# ac-dc-converter-hw.net
KiCad netlist of a schematic drawn in Altium Designer
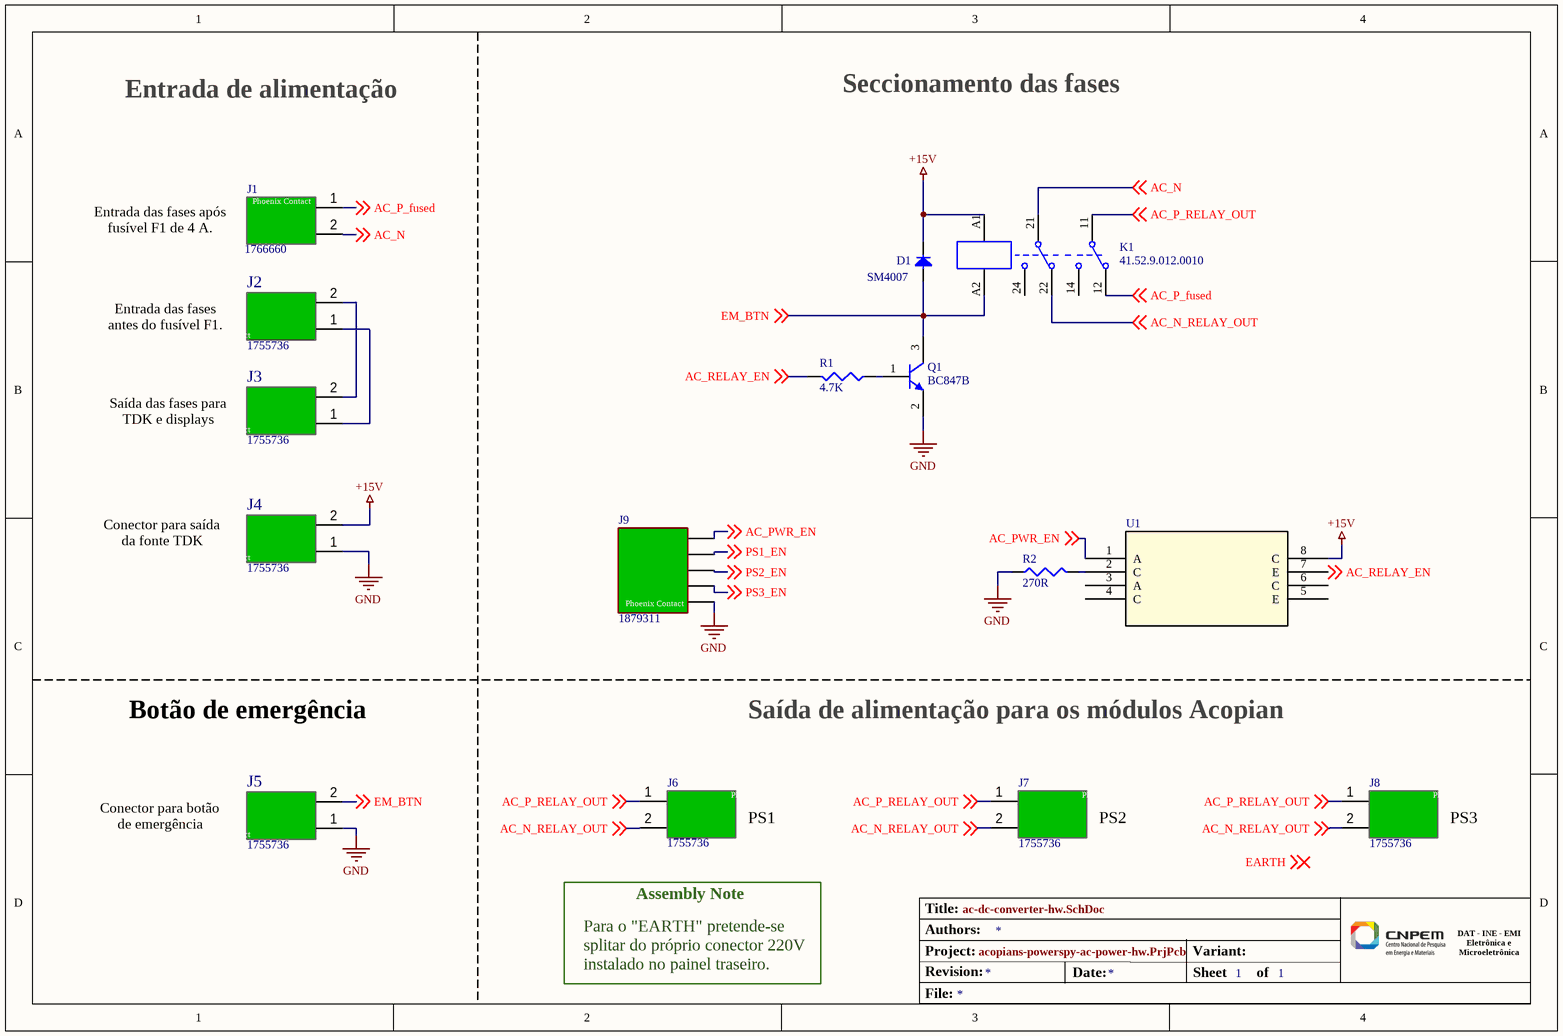
[diagram p0: ac-dc-converter-hw.SchDoc]

(export (version "E")
  (design (tool "Eeschema 10.0.6"))
  (components
    (comp (ref "D1")
      (value "SM4007")
      (footprint "SM4007")
      (libsource (lib "acopians-powerspy-ac-power-hw-library-schematic") (part "SM4007"))
    )
    (comp (ref "J1")
      (value "1766660")
      (footprint "Conector 2 vias espaÃ§ado")
      (description "Pitch 7.5mm")
      (libsource (lib "acopians-powerspy-ac-power-hw-library-schematic") (part "Conector Phoenix 2 vias_espaçado"))
    )
    (comp (ref "J2")
      (value "1755736")
      (footprint "Conector 2 vias")
      (libsource (lib "acopians-powerspy-ac-power-hw-library-schematic") (part "Conector Phoenix 2 vias"))
    )
    (comp (ref "J3")
      (value "1755736")
      (footprint "Conector 2 vias")
      (libsource (lib "acopians-powerspy-ac-power-hw-library-schematic") (part "Conector Phoenix 2 vias"))
    )
    (comp (ref "J4")
      (value "1755736")
      (footprint "Conector 2 vias")
      (libsource (lib "acopians-powerspy-ac-power-hw-library-schematic") (part "Conector Phoenix 2 vias"))
    )
    (comp (ref "J5")
      (value "1755736")
      (footprint "Conector 2 vias")
      (libsource (lib "acopians-powerspy-ac-power-hw-library-schematic") (part "Conector Phoenix 2 vias"))
    )
    (comp (ref "J6")
      (value "1755736")
      (footprint "Conector 2 vias")
      (libsource (lib "") (part "Conector Phoenix 2 vias_1"))
    )
    (comp (ref "J7")
      (value "1755736")
      (footprint "Conector 2 vias")
      (libsource (lib "") (part "Conector Phoenix 2 vias_1"))
    )
    (comp (ref "J8")
      (value "1755736")
      (footprint "Conector 2 vias")
      (libsource (lib "") (part "Conector Phoenix 2 vias_1"))
    )
    (comp (ref "J9")
      (value "1879311")
      (footprint "Conector Phoenix 5 vias 1879311")
      (description "Conector Phoenix 5 vias 1879311")
      (libsource (lib "acopians-powerspy-ac-power-hw-library-schematic") (part "CONECTOR PHOENIX 5 VIAS 1879311"))
    )
    (comp (ref "K1")
      (value "41.52.9.012.0010")
      (footprint "41.52.9.005.0010")
      (description "Low Profile PCB Relay, 2 CO DPDT, 8A, Coil: 12VDC")
      (libsource (lib "acopians-powerspy-ac-power-hw-library-schematic") (part "41.52.9.012.0010"))
    )
    (comp (ref "Q1")
      (value "BC847B")
      (footprint "INF-SOT23_L")
      (description "NPN Silicon AF Transistor, 45 V VCEO, 100 mA IC, SOT23, Reel, Green")
      (fields (field (name "MANUFACTURER") "Infineon"))
      (libsource (lib "Altium Content Vault") (part "INF-BJTNPN-BEC-3"))
    )
    (comp (ref "R1")
      (value "4.7K")
      (footprint "R0603")
      (description "MCT06030C4701FP500")
      (libsource (lib "acopians-powerspy-ac-power-hw-library-schematic") (part "Resistor Generic"))
    )
    (comp (ref "R2")
      (value "270R")
      (footprint "R0603")
      (description "Resistor SMD 270 OHM 1% 1/10W 0603")
      (fields (field (name "TOLERANCE") "1%"))
      (libsource (lib "acopians-monitoring-hw-library-schematic") (part "RESISTOR 270R"))
    )
    (comp (ref "U1")
      (value "~")
      (footprint "SO-8_ILD")
      (description "No Description Available")
      (libsource (lib "acopians-powerspy-ac-power-hw-library-schematic") (part "ILD217T"))
    )
  )
  (nets
    (net (code "1") (name "+15V") (class "Default")
      (node (ref "D1") (pin "1") (pintype "passive"))
      (node (ref "J4") (pin "2") (pinfunction "2_2") (pintype "passive"))
      (node (ref "K1") (pin "A1") (pinfunction "A1_A1") (pintype "passive"))
      (node (ref "U1") (pin "8") (pinfunction "C_8") (pintype "passive"))
    )
    (net (code "2") (name "AC_N") (class "Default")
      (node (ref "J1") (pin "2") (pinfunction "2_2") (pintype "passive"))
      (node (ref "K1") (pin "21") (pinfunction "21_21") (pintype "passive"))
    )
    (net (code "3") (name "AC_N_RELAY_OUT") (class "Default")
      (node (ref "J6") (pin "2") (pinfunction "2_2") (pintype "passive"))
      (node (ref "J7") (pin "2") (pinfunction "2_2") (pintype "passive"))
      (node (ref "J8") (pin "2") (pinfunction "2_2") (pintype "passive"))
      (node (ref "K1") (pin "22") (pinfunction "22_22") (pintype "passive"))
    )
    (net (code "4") (name "AC_PWR_EN") (class "Default")
      (node (ref "J9") (pin "1") (pinfunction "1_1") (pintype "passive"))
      (node (ref "U1") (pin "1") (pinfunction "A_1") (pintype "passive"))
    )
    (net (code "5") (name "AC_P_RELAY_OUT") (class "Default")
      (node (ref "J6") (pin "1") (pinfunction "1_1") (pintype "passive"))
      (node (ref "J7") (pin "1") (pinfunction "1_1") (pintype "passive"))
      (node (ref "J8") (pin "1") (pinfunction "1_1") (pintype "passive"))
      (node (ref "K1") (pin "11") (pinfunction "11_11") (pintype "passive"))
    )
    (net (code "6") (name "AC_P_fused") (class "Default")
      (node (ref "J1") (pin "1") (pinfunction "1_1") (pintype "passive"))
      (node (ref "K1") (pin "12") (pinfunction "12_12") (pintype "passive"))
    )
    (net (code "7") (name "AC_RELAY_EN") (class "Default")
      (node (ref "R1") (pin "2") (pinfunction "2_2") (pintype "passive"))
      (node (ref "U1") (pin "7") (pinfunction "E_7") (pintype "passive"))
    )
    (net (code "9") (name "EM_BTN") (class "Default")
      (node (ref "D1") (pin "2") (pintype "passive"))
      (node (ref "J5") (pin "2") (pinfunction "2_2") (pintype "passive"))
      (node (ref "K1") (pin "A2") (pinfunction "A2_A2") (pintype "passive"))
      (node (ref "Q1") (pin "3") (pinfunction "C_3") (pintype "passive"))
    )
    (net (code "10") (name "GND") (class "Default")
      (node (ref "J4") (pin "1") (pinfunction "1_1") (pintype "passive"))
      (node (ref "J5") (pin "1") (pinfunction "1_1") (pintype "passive"))
      (node (ref "J9") (pin "5") (pinfunction "5_5") (pintype "passive"))
      (node (ref "Q1") (pin "2") (pinfunction "E_2") (pintype "passive"))
      (node (ref "R2") (pin "1") (pinfunction "1_1") (pintype "passive"))
    )
    (net (code "11") (name "Net-(J2-Pad1)") (class "Default")
      (node (ref "J2") (pin "1") (pinfunction "1_1") (pintype "passive"))
      (node (ref "J3") (pin "1") (pinfunction "1_1") (pintype "passive"))
    )
    (net (code "12") (name "Net-(J2-Pad2)") (class "Default")
      (node (ref "J2") (pin "2") (pinfunction "2_2") (pintype "passive"))
      (node (ref "J3") (pin "2") (pinfunction "2_2") (pintype "passive"))
    )
    (net (code "13") (name "Net-(Q1-B)") (class "Default")
      (node (ref "Q1") (pin "1") (pinfunction "B_1") (pintype "passive"))
      (node (ref "R1") (pin "1") (pinfunction "1_1") (pintype "passive"))
    )
    (net (code "14") (name "Net-(R2-Pad2)") (class "Default")
      (node (ref "R2") (pin "2") (pinfunction "2_2") (pintype "passive"))
      (node (ref "U1") (pin "2") (pinfunction "C_2") (pintype "passive"))
    )
    (net (code "15") (name "PS1_EN") (class "Default")
      (node (ref "J9") (pin "2") (pinfunction "2_2") (pintype "passive"))
    )
    (net (code "16") (name "PS2_EN") (class "Default")
      (node (ref "J9") (pin "3") (pinfunction "3_3") (pintype "passive"))
    )
    (net (code "17") (name "PS3_EN") (class "Default")
      (node (ref "J9") (pin "4") (pinfunction "4_4") (pintype "passive"))
    )
    (net (code "18") (name "unconnected-(K1-Pad14)") (class "Default")
      (node (ref "K1") (pin "14") (pinfunction "14_14") (pintype "passive"))
    )
    (net (code "19") (name "unconnected-(K1-Pad24)") (class "Default")
      (node (ref "K1") (pin "24") (pinfunction "24_24") (pintype "passive"))
    )
    (net (code "20") (name "unconnected-(U1-A-Pad3)") (class "Default")
      (node (ref "U1") (pin "3") (pinfunction "A_3") (pintype "passive"))
    )
    (net (code "21") (name "unconnected-(U1-C-Pad4)") (class "Default")
      (node (ref "U1") (pin "4") (pinfunction "C_4") (pintype "passive"))
    )
    (net (code "22") (name "unconnected-(U1-C-Pad6)") (class "Default")
      (node (ref "U1") (pin "6") (pinfunction "C_6") (pintype "passive"))
    )
    (net (code "23") (name "unconnected-(U1-E-Pad5)") (class "Default")
      (node (ref "U1") (pin "5") (pinfunction "E_5") (pintype "passive"))
    )
  )
)
